# harp_camera_controller_v_1_1.net
KiCad netlist of a schematic drawn in EAGLE
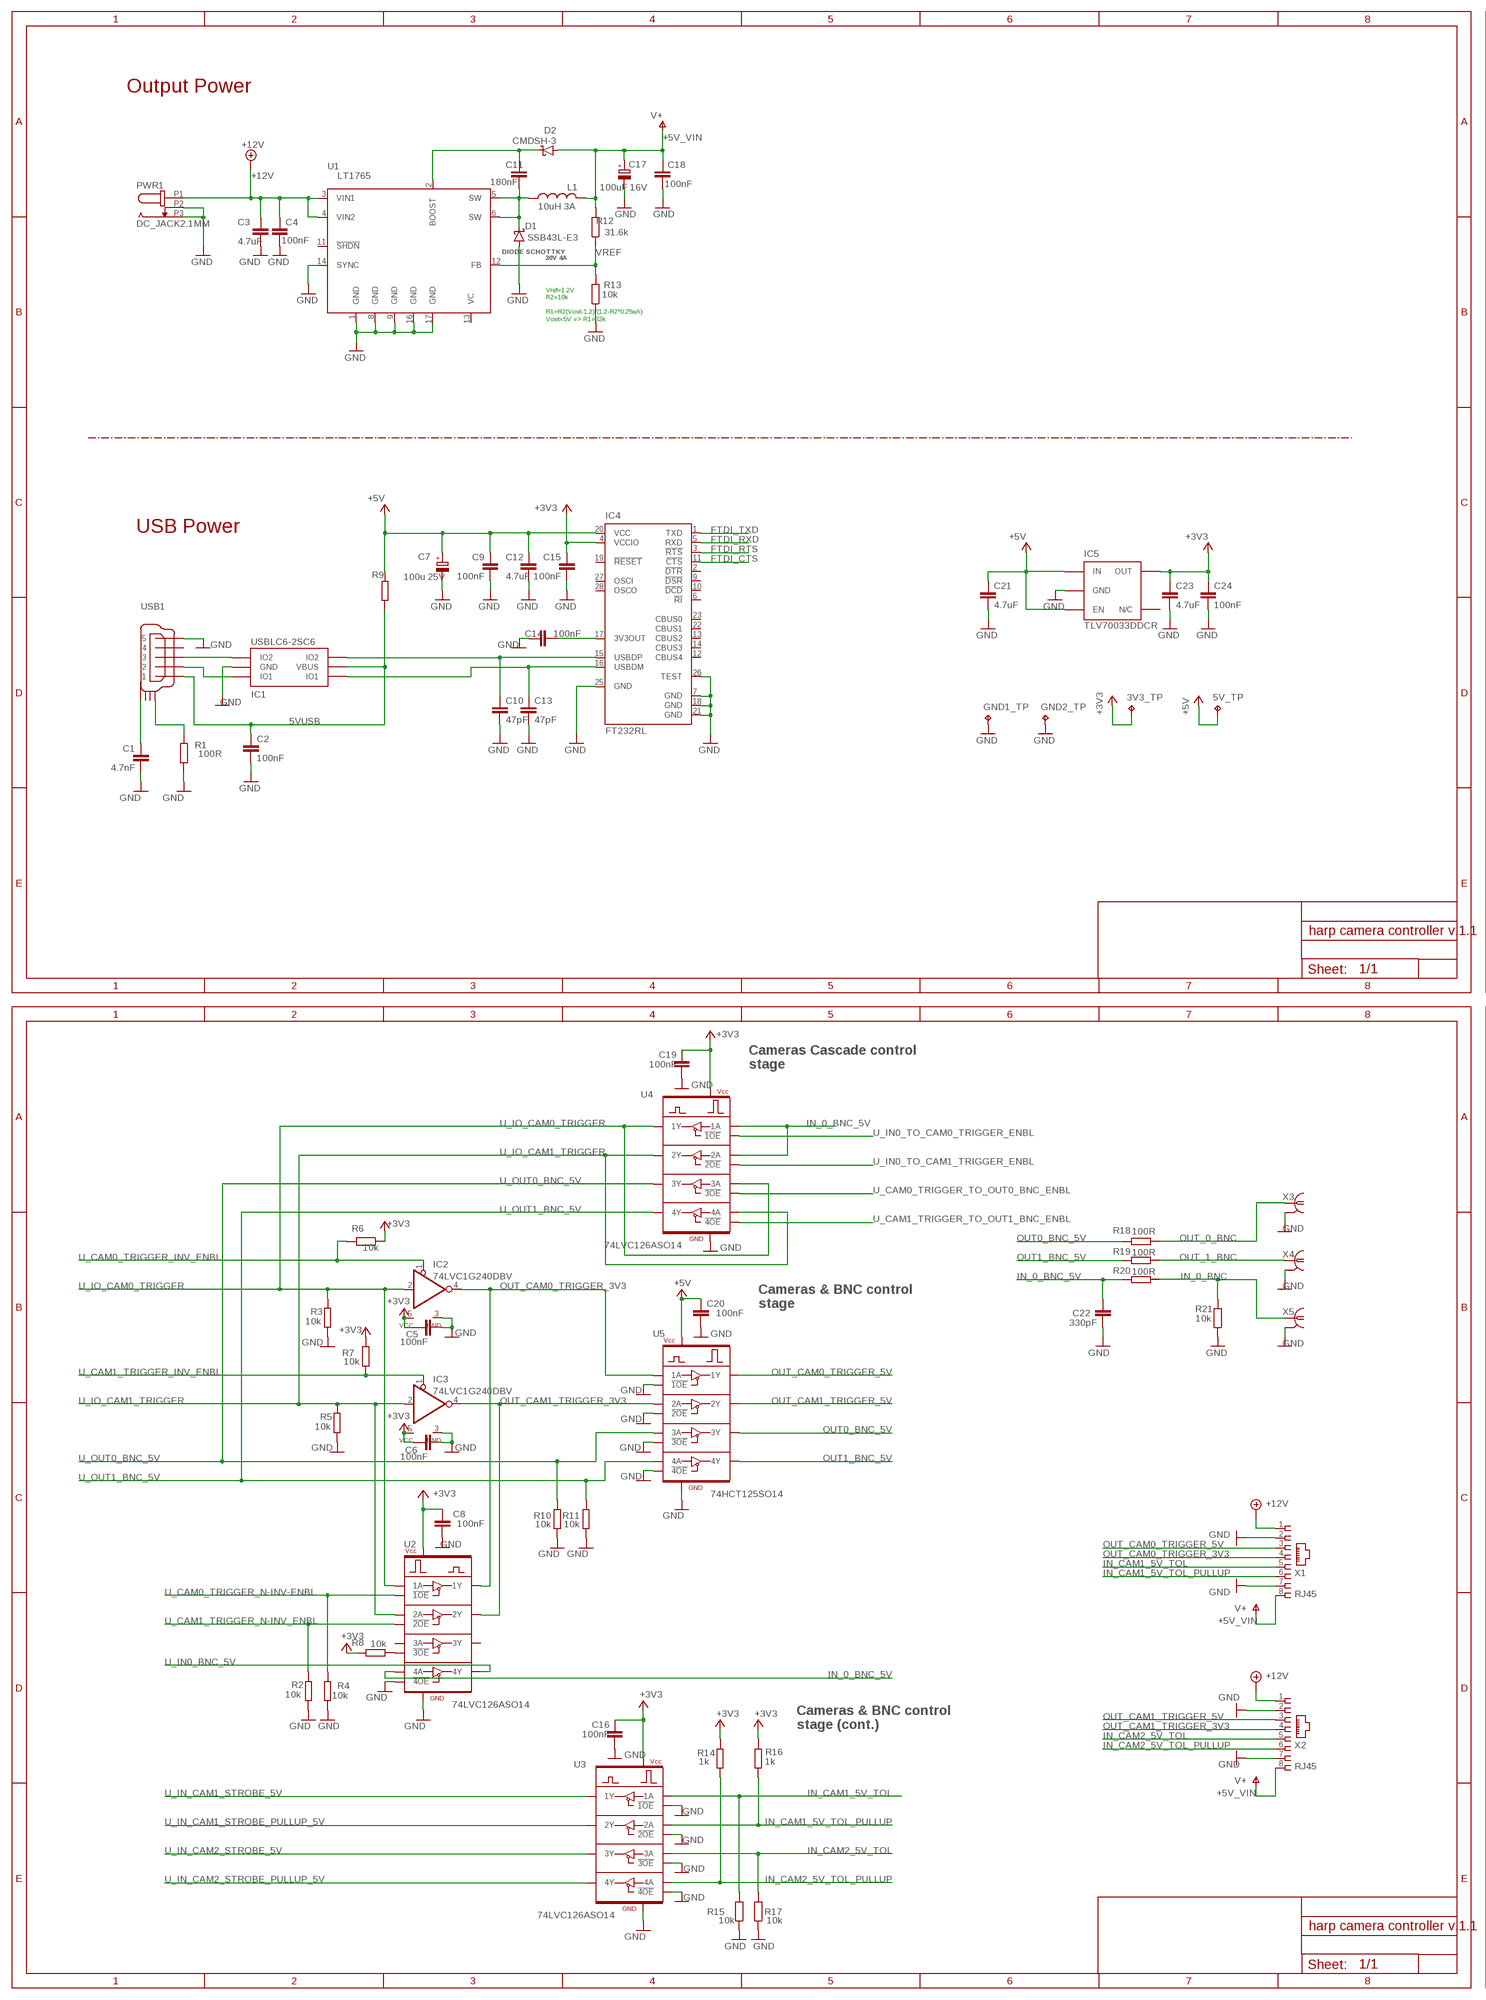
[diagram p0: schematic, sheet 1, part 1 of 2]
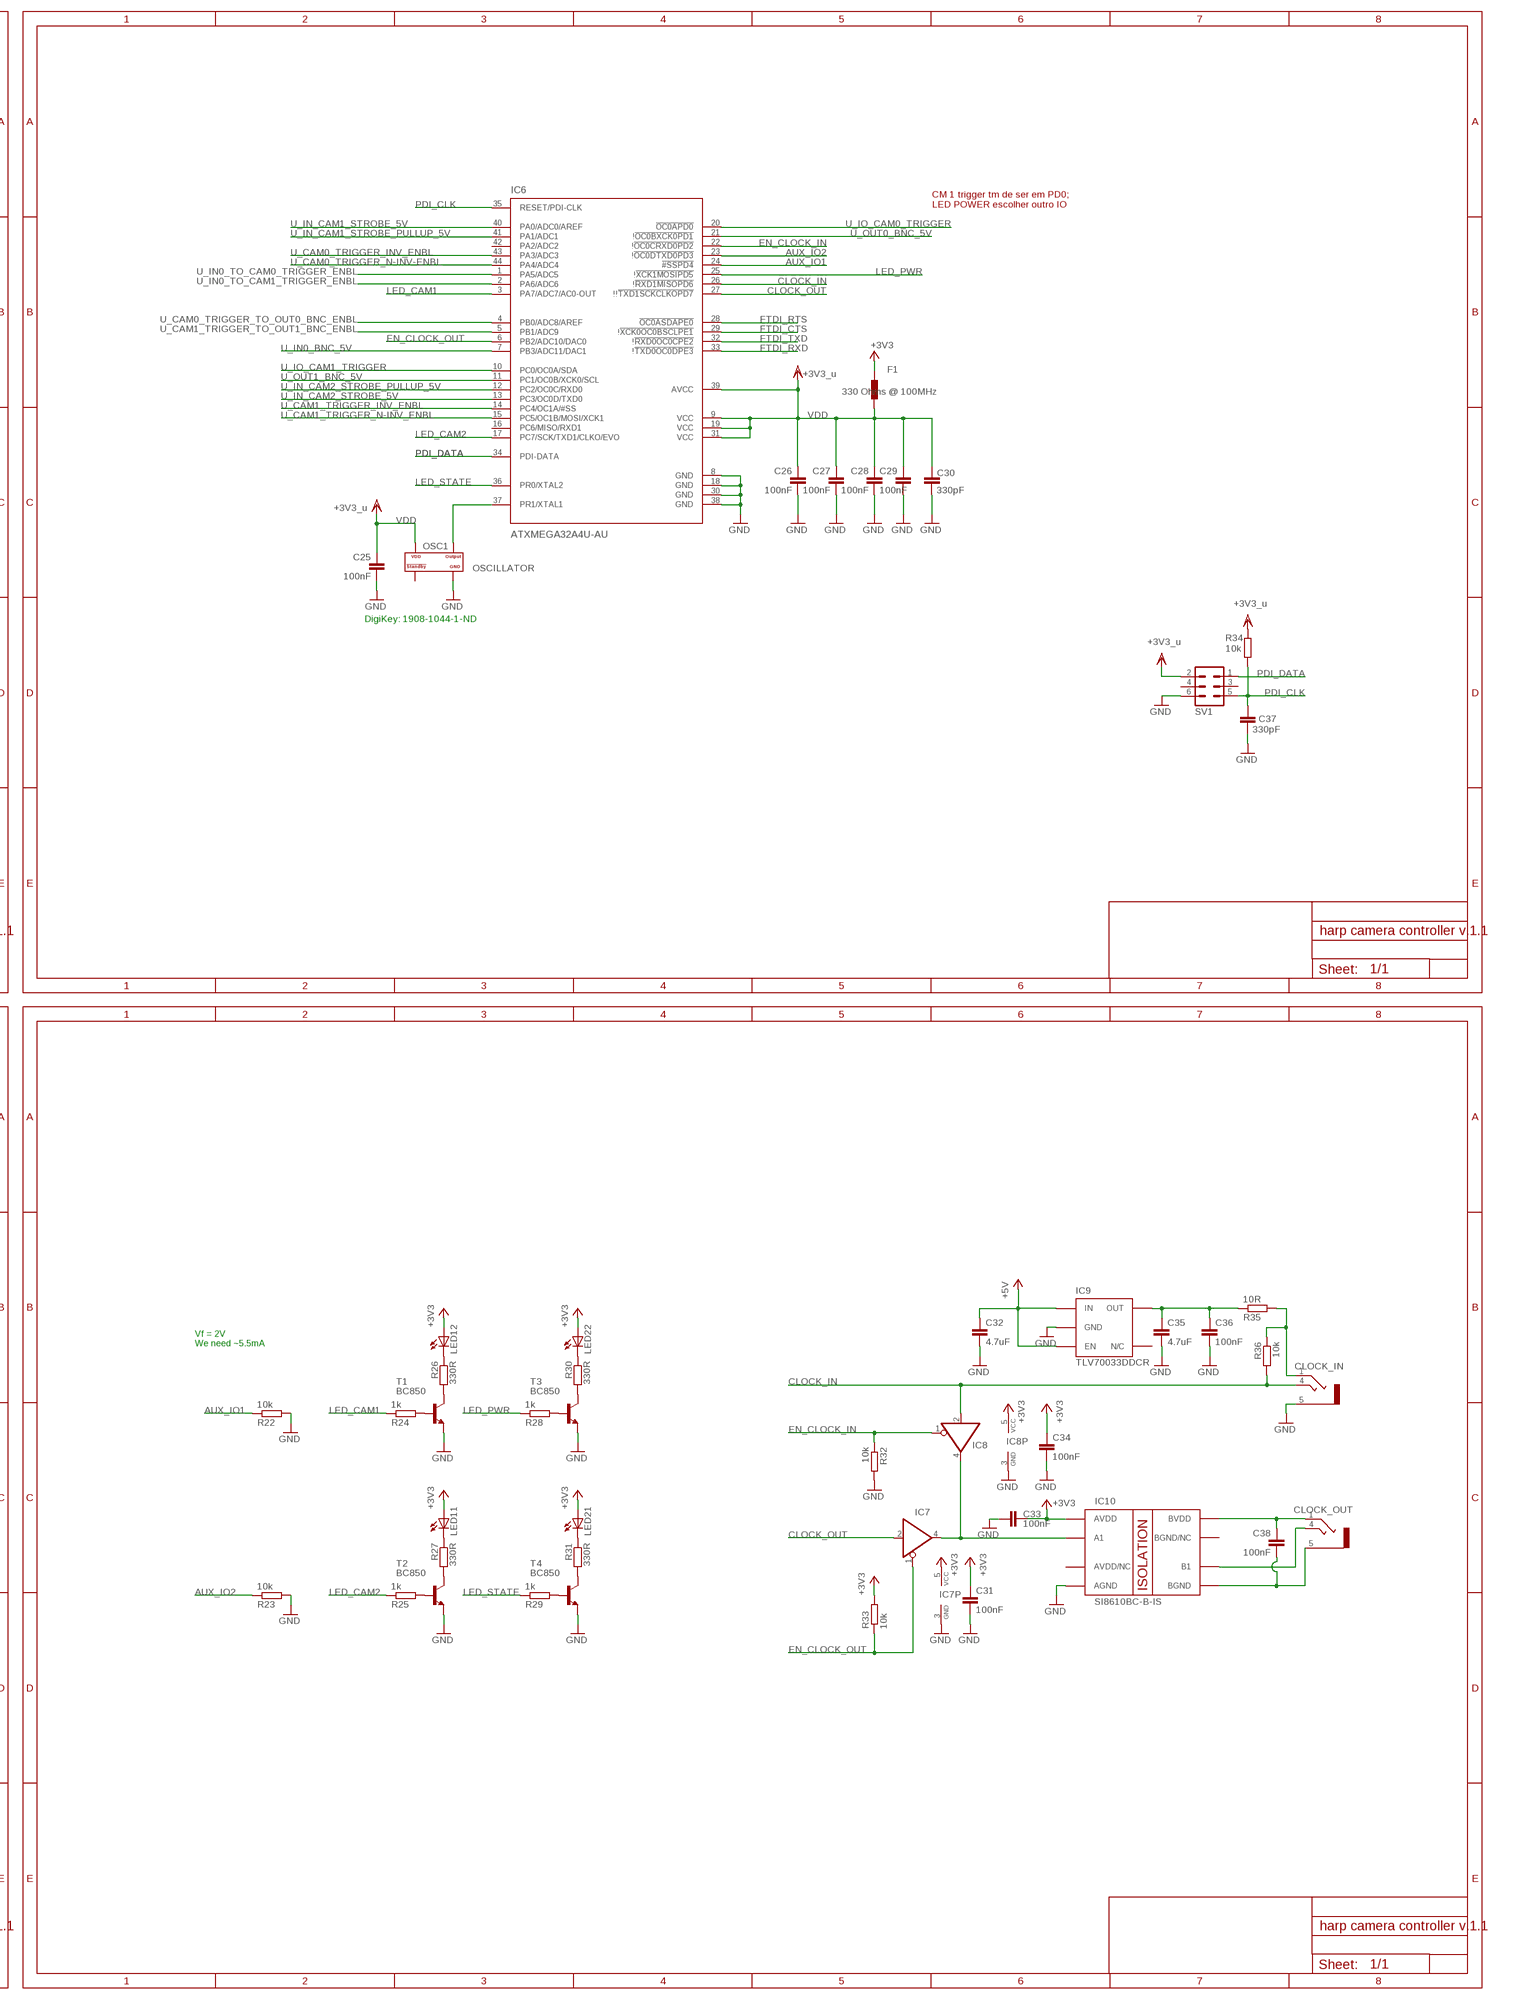
[diagram p1: schematic, sheet 1, part 2 of 2]

(export (version "E")
  (design (tool "Eeschema 10.0.6"))
  (components
    (comp (ref "3V3_TP")
      (value "TPPAD1-13")
      (footprint "eagle-import:P1-13")
      (fields (field (name "MPN") "N.A."))
      (libsource (lib "eagle-import") (part "TPPAD1-13"))
    )
    (comp (ref "5V_TP")
      (value "TPPAD1-13")
      (footprint "eagle-import:P1-13")
      (fields (field (name "MPN") "N.A."))
      (libsource (lib "eagle-import") (part "TPPAD1-13"))
    )
    (comp (ref "C1")
      (value "4.7nF")
      (footprint "eagle-import:C0402")
      (fields (field (name "MPN") "885012205084  "))
      (libsource (lib "eagle-import") (part "C-EUC0402"))
    )
    (comp (ref "C2")
      (value "100nF")
      (footprint "eagle-import:C0402")
      (fields (field (name "MPN") "C1005X7R1H104K050BB"))
      (libsource (lib "eagle-import") (part "C-EUC0402"))
    )
    (comp (ref "C3")
      (value "4.7uF")
      (footprint "eagle-import:C0805")
      (fields (field (name "MPN") "CL21A475KLCLQNC"))
      (libsource (lib "eagle-import") (part "C-EUC0805"))
    )
    (comp (ref "C4")
      (value "100nF")
      (footprint "eagle-import:C0402")
      (fields (field (name "MPN") "C1005X7R1H104K050BB"))
      (libsource (lib "eagle-import") (part "C-EUC0402"))
    )
    (comp (ref "C5")
      (value "100nF")
      (footprint "eagle-import:C0402")
      (fields (field (name "MPN") "C1005X7R1H104K050BB"))
      (libsource (lib "eagle-import") (part "C-EUC0402"))
    )
    (comp (ref "C6")
      (value "100nF")
      (footprint "eagle-import:C0402")
      (fields (field (name "MPN") "C1005X7R1H104K050BB"))
      (libsource (lib "eagle-import") (part "C-EUC0402"))
    )
    (comp (ref "C7")
      (value "100u 25V")
      (footprint "eagle-import:TT2D6")
      (fields (field (name "MPN") "EEU-FM1E101B"))
      (libsource (lib "eagle-import") (part "CPOL-EUTT2D6"))
    )
    (comp (ref "C8")
      (value "100nF")
      (footprint "eagle-import:C0402")
      (fields (field (name "MPN") "C1005X7R1H104K050BB"))
      (libsource (lib "eagle-import") (part "C-EUC0402"))
    )
    (comp (ref "C9")
      (value "100nF")
      (footprint "eagle-import:C0402")
      (fields (field (name "MPN") "C1005X7R1H104K050BB"))
      (libsource (lib "eagle-import") (part "C-EUC0402"))
    )
    (comp (ref "C10")
      (value "47pF")
      (footprint "eagle-import:C0402")
      (fields (field (name "MPN") "04025A470JAT2A"))
      (libsource (lib "eagle-import") (part "C-EUC0402"))
    )
    (comp (ref "C11")
      (value "180nF")
      (footprint "eagle-import:C0603")
      (fields (field (name "MPN") "GCG188R91H184KA01D"))
      (libsource (lib "eagle-import") (part "C-EUC0603"))
    )
    (comp (ref "C12")
      (value "4.7uF")
      (footprint "eagle-import:C0603")
      (fields (field (name "MPN") "C1608X6S1C475K080AC"))
      (libsource (lib "eagle-import") (part "C-EUC0603"))
    )
    (comp (ref "C13")
      (value "47pF")
      (footprint "eagle-import:C0402")
      (fields (field (name "MPN") "04025A470JAT2A"))
      (libsource (lib "eagle-import") (part "C-EUC0402"))
    )
    (comp (ref "C14")
      (value "100nF")
      (footprint "eagle-import:C0402")
      (fields (field (name "MPN") "C1005X7R1H104K050BB"))
      (libsource (lib "eagle-import") (part "C-EUC0402"))
    )
    (comp (ref "C15")
      (value "100nF")
      (footprint "eagle-import:C0402")
      (fields (field (name "MPN") "C1005X7R1H104K050BB"))
      (libsource (lib "eagle-import") (part "C-EUC0402"))
    )
    (comp (ref "C16")
      (value "100nF")
      (footprint "eagle-import:C0402")
      (fields (field (name "MPN") "C1005X7R1H104K050BB"))
      (libsource (lib "eagle-import") (part "C-EUC0402"))
    )
    (comp (ref "C17")
      (value "100uF 16V")
      (footprint "eagle-import:CT7343")
      (fields (field (name "MPN") "T491D107K016AT7280"))
      (libsource (lib "eagle-import") (part "CPOL-EUCT7343"))
    )
    (comp (ref "C18")
      (value "100nF")
      (footprint "eagle-import:C0402")
      (fields (field (name "MPN") "C1005X7R1H104K050BB"))
      (libsource (lib "eagle-import") (part "C-EUC0402"))
    )
    (comp (ref "C19")
      (value "100nF")
      (footprint "eagle-import:C0402")
      (fields (field (name "MPN") "C1005X7R1H104K050BB"))
      (libsource (lib "eagle-import") (part "C-EUC0402"))
    )
    (comp (ref "C20")
      (value "100nF")
      (footprint "eagle-import:C0402")
      (fields (field (name "MPN") "C1005X7R1H104K050BB"))
      (libsource (lib "eagle-import") (part "C-EUC0402"))
    )
    (comp (ref "C21")
      (value "4.7uF")
      (footprint "eagle-import:C0603")
      (fields (field (name "MPN") "C1608X6S1C475K080AC"))
      (libsource (lib "eagle-import") (part "C-EUC0603"))
    )
    (comp (ref "C22")
      (value "330pF")
      (footprint "eagle-import:C0402")
      (fields (field (name "MPN") "C0402C331J5GACTU"))
      (libsource (lib "eagle-import") (part "C-EUC0402"))
    )
    (comp (ref "C23")
      (value "4.7uF")
      (footprint "eagle-import:C0603")
      (fields (field (name "MPN") "C1608X6S1C475K080AC"))
      (libsource (lib "eagle-import") (part "C-EUC0603"))
    )
    (comp (ref "C24")
      (value "100nF")
      (footprint "eagle-import:C0402")
      (fields (field (name "MPN") "C1005X7R1H104K050BB"))
      (libsource (lib "eagle-import") (part "C-EUC0402"))
    )
    (comp (ref "C25")
      (value "100nF")
      (footprint "eagle-import:C0402")
      (fields (field (name "MPN") "C1005X7R1H104K050BB"))
      (libsource (lib "eagle-import") (part "C-EUC0402"))
    )
    (comp (ref "C26")
      (value "100nF")
      (footprint "eagle-import:C0402")
      (fields (field (name "MPN") "C1005X7R1H104K050BB"))
      (libsource (lib "eagle-import") (part "C-EUC0402"))
    )
    (comp (ref "C27")
      (value "100nF")
      (footprint "eagle-import:C0402")
      (fields (field (name "MPN") "C1005X7R1H104K050BB"))
      (libsource (lib "eagle-import") (part "C-EUC0402"))
    )
    (comp (ref "C28")
      (value "100nF")
      (footprint "eagle-import:C0402")
      (fields (field (name "MPN") "C1005X7R1H104K050BB"))
      (libsource (lib "eagle-import") (part "C-EUC0402"))
    )
    (comp (ref "C29")
      (value "100nF")
      (footprint "eagle-import:C0402")
      (fields (field (name "MPN") "C1005X7R1H104K050BB"))
      (libsource (lib "eagle-import") (part "C-EUC0402"))
    )
    (comp (ref "C30")
      (value "330pF")
      (footprint "eagle-import:C0402")
      (fields (field (name "MPN") "C0402C331J5GACTU"))
      (libsource (lib "eagle-import") (part "C-EUC0402"))
    )
    (comp (ref "C31")
      (value "100nF")
      (footprint "eagle-import:C0402")
      (fields (field (name "MPN") "C1005X7R1H104K050BB"))
      (libsource (lib "eagle-import") (part "C-EUC0402"))
    )
    (comp (ref "C32")
      (value "4.7uF")
      (footprint "eagle-import:C0603")
      (fields (field (name "MPN") "C1608X6S1C475K080AC"))
      (libsource (lib "eagle-import") (part "C-EUC0603"))
    )
    (comp (ref "C33")
      (value "100nF")
      (footprint "eagle-import:C0402")
      (fields (field (name "MPN") "C1005X7R1H104K050BB"))
      (libsource (lib "eagle-import") (part "C-EUC0402"))
    )
    (comp (ref "C34")
      (value "100nF")
      (footprint "eagle-import:C0402")
      (fields (field (name "MPN") "C1005X7R1H104K050BB"))
      (libsource (lib "eagle-import") (part "C-EUC0402"))
    )
    (comp (ref "C35")
      (value "4.7uF")
      (footprint "eagle-import:C0603")
      (fields (field (name "MPN") "C1608X6S1C475K080AC"))
      (libsource (lib "eagle-import") (part "C-EUC0603"))
    )
    (comp (ref "C36")
      (value "100nF")
      (footprint "eagle-import:C0402")
      (fields (field (name "MPN") "C1005X7R1H104K050BB"))
      (libsource (lib "eagle-import") (part "C-EUC0402"))
    )
    (comp (ref "C37")
      (value "330pF")
      (footprint "eagle-import:C0402")
      (fields (field (name "MPN") "C0402C331J5GACTU"))
      (libsource (lib "eagle-import") (part "C-EUC0402"))
    )
    (comp (ref "C38")
      (value "100nF")
      (footprint "eagle-import:C0402")
      (fields (field (name "MPN") "C1005X7R1H104K050BB"))
      (libsource (lib "eagle-import") (part "C-EUC0402"))
    )
    (comp (ref "CLOCK_IN")
      (value "CLCK_JACK")
      (footprint "eagle-import:35RASMT2BHNTRX")
      (fields (field (name "MPN") "35RASMT2BHNTRX"))
      (libsource (lib "eagle-import") (part "STEREO_JACK"))
    )
    (comp (ref "CLOCK_OUT")
      (value "CLCK_JACK")
      (footprint "eagle-import:35RASMT2BHNTRX")
      (fields (field (name "MPN") "35RASMT2BHNTRX"))
      (libsource (lib "eagle-import") (part "STEREO_JACK"))
    )
    (comp (ref "D1")
      (value "SSB43L-E3")
      (footprint "eagle-import:SMB")
      (fields (field (name "MPN") "SSB43L-E3/52T"))
      (libsource (lib "eagle-import") (part "SCHOTTKY-DIODE"))
    )
    (comp (ref "D2")
      (value "CMDSH-3")
      (footprint "eagle-import:SOD323-R")
      (libsource (lib "eagle-import") (part "SCHOTTKY-DIODESOD323"))
    )
    (comp (ref "F1")
      (value "330 Ohms @ 100MHz")
      (footprint "eagle-import:R0603")
      (fields (field (name "MPN") "BLM18SG331TN1D"))
      (libsource (lib "eagle-import") (part "BLM15HF0603"))
    )
    (comp (ref "GND1_TP")
      (value "TPPAD1-13")
      (footprint "eagle-import:P1-13")
      (fields (field (name "MPN") "N.A."))
      (libsource (lib "eagle-import") (part "TPPAD1-13"))
    )
    (comp (ref "GND2_TP")
      (value "TPPAD1-13")
      (footprint "eagle-import:P1-13")
      (fields (field (name "MPN") "N.A."))
      (libsource (lib "eagle-import") (part "TPPAD1-13"))
    )
    (comp (ref "IC1")
      (value "USBLC6-2SC6")
      (footprint "eagle-import:SOT23-6L")
      (libsource (lib "eagle-import") (part "USBLC6-2"))
    )
    (comp (ref "IC2")
      (value "74LVC1G240DBV")
      (footprint "eagle-import:SOT23-5")
      (fields (field (name "MPN") "SN74LVC1G240DBVR"))
      (libsource (lib "eagle-import") (part "74LVC1G240DBV"))
    )
    (comp (ref "IC3")
      (value "74LVC1G240DBV")
      (footprint "eagle-import:SOT23-5")
      (fields (field (name "MPN") "SN74LVC1G240DBVR"))
      (libsource (lib "eagle-import") (part "74LVC1G240DBV"))
    )
    (comp (ref "IC4")
      (value "FT232RL")
      (footprint "eagle-import:SSOP28")
      (fields (field (name "MPN") "FT232RL-REEL"))
      (libsource (lib "eagle-import") (part "FT232RL"))
    )
    (comp (ref "IC5")
      (value "TLV70033DDCR")
      (footprint "eagle-import:TSOT23-5")
      (libsource (lib "eagle-import") (part "TLV700XX"))
    )
    (comp (ref "IC6")
      (value "ATXMEGA32A4U-AU")
      (footprint "eagle-import:QFP80P1200X1200X120-44N")
      (fields (field (name "MPN") "ATXMEGA32A4U-AUR"))
      (libsource (lib "eagle-import") (part "AT-XMEGA-XXA4-AU"))
    )
    (comp (ref "IC7")
      (value "SN74LVC1G125DBVT")
      (footprint "eagle-import:SOT23-5")
      (fields
        (field (name "DIGIKEY_PN") "296-26595-1-ND")
        (field (name "MOUSER_PN") "595-SN74LVC1G125DBVT")
        (field (name "MPN") "SN74LVC1G125DBVT")
      )
      (libsource (lib "eagle-import") (part "741G125DBVAHC"))
    )
    (comp (ref "IC8")
      (value "SN74LVC1G125DBVT")
      (footprint "eagle-import:SOT23-5")
      (fields
        (field (name "DIGIKEY_PN") "296-26595-1-ND")
        (field (name "MOUSER_PN") "595-SN74LVC1G125DBVT")
        (field (name "MPN") "SN74LVC1G125DBVT")
      )
      (libsource (lib "eagle-import") (part "741G125DBVAHC"))
    )
    (comp (ref "IC9")
      (value "TLV70033DDCR")
      (footprint "eagle-import:TSOT23-5")
      (libsource (lib "eagle-import") (part "TLV700XX"))
    )
    (comp (ref "IC10")
      (value "SI8610BC-B-IS")
      (footprint "eagle-import:SO-08")
      (fields (field (name "MPN") "SI8610EC-B-IS"))
      (libsource (lib "eagle-import") (part "SI8610"))
    )
    (comp (ref "L1")
      (value "10uH 3A")
      (footprint "eagle-import:L_IHLP_PADS")
      (fields (field (name "MPN") "IHLP2525CZER100M01"))
      (libsource (lib "eagle-import") (part "L_IHLP2525CZER100M01"))
    )
    (comp (ref "LED1")
      (value "RED_LEDs")
      (footprint "eagle-import:569-011X-X00_LED_ARRAY")
      (fields (field (name "MPN") "5690-111-100F"))
      (libsource (lib "eagle-import") (part "LED_2X_VERTICAL"))
    )
    (comp (ref "LED2")
      (value "RED_LEDs")
      (footprint "eagle-import:569-011X-X00_LED_ARRAY")
      (fields (field (name "MPN") "5690-111-100F"))
      (libsource (lib "eagle-import") (part "LED_2X_VERTICAL"))
    )
    (comp (ref "OSC1")
      (value "OSCILLATOR")
      (footprint "eagle-import:OSCILLATOR_3.2X2.5")
      (fields (field (name "MPN") "O 32,0-JT32C-A-K-3,3-LF"))
      (libsource (lib "eagle-import") (part "OSCILLATOR"))
    )
    (comp (ref "PWR1")
      (value "DC_JACK2.1MM")
      (footprint "eagle-import:DC_POWER_INPUT_2.1MM")
      (fields (field (name "MPN") "163-179PH-EX"))
      (libsource (lib "eagle-import") (part "DC_JACK2.1MM"))
    )
    (comp (ref "R1")
      (value "100R")
      (footprint "eagle-import:R0603")
      (fields (field (name "MPN") "ERJ-3EKF1000V"))
      (libsource (lib "eagle-import") (part "R-EU_R0603"))
    )
    (comp (ref "R2")
      (value "10k")
      (footprint "eagle-import:R0402")
      (fields (field (name "MPN") "CRCW040210K0FKED"))
      (libsource (lib "eagle-import") (part "R-EU_R0402"))
    )
    (comp (ref "R3")
      (value "10k")
      (footprint "eagle-import:R0402")
      (fields (field (name "MPN") "CRCW040210K0FKED"))
      (libsource (lib "eagle-import") (part "R-EU_R0402"))
    )
    (comp (ref "R4")
      (value "10k")
      (footprint "eagle-import:R0402")
      (fields (field (name "MPN") "CRCW040210K0FKED"))
      (libsource (lib "eagle-import") (part "R-EU_R0402"))
    )
    (comp (ref "R5")
      (value "10k")
      (footprint "eagle-import:R0402")
      (fields (field (name "MPN") "CRCW040210K0FKED"))
      (libsource (lib "eagle-import") (part "R-EU_R0402"))
    )
    (comp (ref "R6")
      (value "10k")
      (footprint "eagle-import:R0402")
      (fields (field (name "MPN") "CRCW040210K0FKED"))
      (libsource (lib "eagle-import") (part "R-EU_R0402"))
    )
    (comp (ref "R7")
      (value "10k")
      (footprint "eagle-import:R0402")
      (fields (field (name "MPN") "CRCW040210K0FKED"))
      (libsource (lib "eagle-import") (part "R-EU_R0402"))
    )
    (comp (ref "R8")
      (value "10k")
      (footprint "eagle-import:R0402")
      (fields (field (name "MPN") "CRCW040210K0FKED"))
      (libsource (lib "eagle-import") (part "R-EU_R0402"))
    )
    (comp (ref "R9")
      (value "40R@100MHz")
      (footprint "eagle-import:R0805")
      (fields (field (name "MPN") "MI0805K400R-10"))
      (libsource (lib "eagle-import") (part "R-EU_R0805"))
    )
    (comp (ref "R10")
      (value "10k")
      (footprint "eagle-import:R0402")
      (fields (field (name "MPN") "CRCW040210K0FKED"))
      (libsource (lib "eagle-import") (part "R-EU_R0402"))
    )
    (comp (ref "R11")
      (value "10k")
      (footprint "eagle-import:R0402")
      (fields (field (name "MPN") "CRCW040210K0FKED"))
      (libsource (lib "eagle-import") (part "R-EU_R0402"))
    )
    (comp (ref "R12")
      (value "31.6k")
      (footprint "eagle-import:R0402")
      (fields (field (name "MPN") "RC0402FR-0740K2L"))
      (libsource (lib "eagle-import") (part "R-EU_R0402"))
    )
    (comp (ref "R13")
      (value "10k")
      (footprint "eagle-import:R0402")
      (fields (field (name "MPN") "CRCW040210K0FKED"))
      (libsource (lib "eagle-import") (part "R-EU_R0402"))
    )
    (comp (ref "R14")
      (value "1k")
      (footprint "eagle-import:R0402")
      (fields (field (name "MPN") "CRCW04021K00FKEDC"))
      (libsource (lib "eagle-import") (part "R-EU_R0402"))
    )
    (comp (ref "R15")
      (value "10k")
      (footprint "eagle-import:R0402")
      (fields (field (name "MPN") "CRCW040210K0FKED"))
      (libsource (lib "eagle-import") (part "R-EU_R0402"))
    )
    (comp (ref "R16")
      (value "1k")
      (footprint "eagle-import:R0402")
      (fields (field (name "MPN") "CRCW04021K00FKEDC"))
      (libsource (lib "eagle-import") (part "R-EU_R0402"))
    )
    (comp (ref "R17")
      (value "10k")
      (footprint "eagle-import:R0402")
      (fields (field (name "MPN") "CRCW040210K0FKED"))
      (libsource (lib "eagle-import") (part "R-EU_R0402"))
    )
    (comp (ref "R18")
      (value "100R")
      (footprint "eagle-import:R0603")
      (fields (field (name "MPN") "ERJ-3EKF1000V"))
      (libsource (lib "eagle-import") (part "R-EU_R0603"))
    )
    (comp (ref "R19")
      (value "100R")
      (footprint "eagle-import:R0603")
      (fields (field (name "MPN") "ERJ-3EKF1000V"))
      (libsource (lib "eagle-import") (part "R-EU_R0603"))
    )
    (comp (ref "R20")
      (value "100R")
      (footprint "eagle-import:R0603")
      (fields (field (name "MPN") "ERJ-3EKF1000V"))
      (libsource (lib "eagle-import") (part "R-EU_R0603"))
    )
    (comp (ref "R21")
      (value "10k")
      (footprint "eagle-import:R0402")
      (fields (field (name "MPN") "CRCW040210K0FKED"))
      (libsource (lib "eagle-import") (part "R-EU_R0402"))
    )
    (comp (ref "R22")
      (value "10k")
      (footprint "eagle-import:R0402")
      (fields (field (name "MPN") "CRCW040210K0FKED"))
      (libsource (lib "eagle-import") (part "R-EU_R0402"))
    )
    (comp (ref "R23")
      (value "10k")
      (footprint "eagle-import:R0402")
      (fields (field (name "MPN") "CRCW040210K0FKED"))
      (libsource (lib "eagle-import") (part "R-EU_R0402"))
    )
    (comp (ref "R24")
      (value "1k")
      (footprint "eagle-import:R0402")
      (fields (field (name "MPN") "CRCW04021K00FKEDC"))
      (libsource (lib "eagle-import") (part "R-EU_R0402"))
    )
    (comp (ref "R25")
      (value "1k")
      (footprint "eagle-import:R0402")
      (fields (field (name "MPN") "CRCW04021K00FKEDC"))
      (libsource (lib "eagle-import") (part "R-EU_R0402"))
    )
    (comp (ref "R26")
      (value "330R")
      (footprint "eagle-import:R0402")
      (fields (field (name "MPN") "RC0402FR-07330RL "))
      (libsource (lib "eagle-import") (part "R-EU_R0402"))
    )
    (comp (ref "R27")
      (value "330R")
      (footprint "eagle-import:R0402")
      (fields (field (name "MPN") "RC0402FR-07330RL "))
      (libsource (lib "eagle-import") (part "R-EU_R0402"))
    )
    (comp (ref "R28")
      (value "1k")
      (footprint "eagle-import:R0402")
      (fields (field (name "MPN") "CRCW04021K00FKEDC"))
      (libsource (lib "eagle-import") (part "R-EU_R0402"))
    )
    (comp (ref "R29")
      (value "1k")
      (footprint "eagle-import:R0402")
      (fields (field (name "MPN") "CRCW04021K00FKEDC"))
      (libsource (lib "eagle-import") (part "R-EU_R0402"))
    )
    (comp (ref "R30")
      (value "330R")
      (footprint "eagle-import:R0402")
      (fields (field (name "MPN") "RC0402FR-07330RL "))
      (libsource (lib "eagle-import") (part "R-EU_R0402"))
    )
    (comp (ref "R31")
      (value "330R")
      (footprint "eagle-import:R0402")
      (fields (field (name "MPN") "RC0402FR-07330RL "))
      (libsource (lib "eagle-import") (part "R-EU_R0402"))
    )
    (comp (ref "R32")
      (value "10k")
      (footprint "eagle-import:R0402")
      (fields (field (name "MPN") "CRCW040210K0FKED"))
      (libsource (lib "eagle-import") (part "R-EU_R0402"))
    )
    (comp (ref "R33")
      (value "10k")
      (footprint "eagle-import:R0402")
      (fields (field (name "MPN") "CRCW040210K0FKED"))
      (libsource (lib "eagle-import") (part "R-EU_R0402"))
    )
    (comp (ref "R34")
      (value "10k")
      (footprint "eagle-import:R0402")
      (fields (field (name "MPN") "CRCW040210K0FKED"))
      (libsource (lib "eagle-import") (part "R-EU_R0402"))
    )
    (comp (ref "R35")
      (value "10R")
      (footprint "eagle-import:R0402")
      (fields (field (name "MPN") "CRCW040210R0FKEDC"))
      (libsource (lib "eagle-import") (part "R-EU_R0402"))
    )
    (comp (ref "R36")
      (value "10k")
      (footprint "eagle-import:R0402")
      (fields (field (name "MPN") "CRCW040210K0FKED"))
      (libsource (lib "eagle-import") (part "R-EU_R0402"))
    )
    (comp (ref "SV1")
      (value "PROG HEADER")
      (footprint "eagle-import:MA03-2")
      (fields (field (name "MPN") "61300621121"))
      (libsource (lib "eagle-import") (part "MA03-2"))
    )
    (comp (ref "T1")
      (value "BC850")
      (footprint "eagle-import:SOT23")
      (fields (field (name "MPN") "BC850C,215"))
      (libsource (lib "eagle-import") (part "BC850"))
    )
    (comp (ref "T2")
      (value "BC850")
      (footprint "eagle-import:SOT23")
      (fields (field (name "MPN") "BC850C,215"))
      (libsource (lib "eagle-import") (part "BC850"))
    )
    (comp (ref "T3")
      (value "BC850")
      (footprint "eagle-import:SOT23")
      (fields (field (name "MPN") "BC850C,215"))
      (libsource (lib "eagle-import") (part "BC850"))
    )
    (comp (ref "T4")
      (value "BC850")
      (footprint "eagle-import:SOT23")
      (fields (field (name "MPN") "BC850C,215"))
      (libsource (lib "eagle-import") (part "BC850"))
    )
    (comp (ref "U1")
      (value "LT1765")
      (footprint "eagle-import:TSSOP16EXP")
      (fields (field (name "MPN") "LT1765EFE#PBF"))
      (libsource (lib "eagle-import") (part "LT1765"))
    )
    (comp (ref "U2")
      (value "74LVC126ASO14")
      (footprint "eagle-import:SO14")
      (fields (field (name "MPN") "74LVC126AD,118  "))
      (libsource (lib "eagle-import") (part "74LVC126ASO14"))
    )
    (comp (ref "U3")
      (value "74LVC126ASO14")
      (footprint "eagle-import:SO14")
      (fields (field (name "MPN") "74LVC126AD,118  "))
      (libsource (lib "eagle-import") (part "74LVC126ASO14"))
    )
    (comp (ref "U4")
      (value "74LVC126ASO14")
      (footprint "eagle-import:SO14")
      (fields (field (name "MPN") "74LVC126AD,118  "))
      (libsource (lib "eagle-import") (part "74LVC126ASO14"))
    )
    (comp (ref "U5")
      (value "74HCT125SO14")
      (footprint "eagle-import:SO14")
      (fields (field (name "MPN") "74HCT125D,653"))
      (libsource (lib "eagle-import") (part "74HCT125SO14"))
    )
    (comp (ref "USB1")
      (value "mini USB")
      (footprint "eagle-import:240-0002-1")
      (fields (field (name "MPN") "UX60-MB-5S8 "))
      (libsource (lib "eagle-import") (part "USB_MINI_B"))
    )
    (comp (ref "X1")
      (value "RJ45")
      (footprint "eagle-import:RJ45-NO-SHIELD")
      (fields (field (name "MPN") "215877-1"))
      (libsource (lib "eagle-import") (part "RJ45"))
    )
    (comp (ref "X2")
      (value "RJ45")
      (footprint "eagle-import:RJ45-NO-SHIELD")
      (fields (field (name "MPN") "215877-1"))
      (libsource (lib "eagle-import") (part "RJ45"))
    )
    (comp (ref "X3")
      (value "BNC plug")
      (footprint "eagle-import:0731000105")
      (fields (field (name "MPN") "73100-0105"))
      (libsource (lib "eagle-import") (part "BNC_0731000105"))
    )
    (comp (ref "X4")
      (value "BNC plug")
      (footprint "eagle-import:0731000105")
      (fields (field (name "MPN") "73100-0105"))
      (libsource (lib "eagle-import") (part "BNC_0731000105"))
    )
    (comp (ref "X5")
      (value "BNC plug")
      (footprint "eagle-import:0731000105")
      (fields (field (name "MPN") "73100-0105"))
      (libsource (lib "eagle-import") (part "BNC_0731000105"))
    )
  )
  (nets
    (net (code "1") (name "+3V3") (class "Default")
      (node (ref "3V3_TP") (pin "TP") (pinfunction "TP_TP") (pintype "input"))
      (node (ref "C15") (pin "1") (pinfunction "1_1") (pintype "passive"))
      (node (ref "C16") (pin "1") (pinfunction "1_1") (pintype "passive"))
      (node (ref "C19") (pin "1") (pinfunction "1_1") (pintype "passive"))
      (node (ref "C23") (pin "1") (pinfunction "1_1") (pintype "passive"))
      (node (ref "C24") (pin "1") (pinfunction "1_1") (pintype "passive"))
      (node (ref "C31") (pin "1") (pinfunction "1_1") (pintype "passive"))
      (node (ref "C33") (pin "1") (pinfunction "1_1") (pintype "passive"))
      (node (ref "C34") (pin "1") (pinfunction "1_1") (pintype "passive"))
      (node (ref "C5") (pin "1") (pinfunction "1_1") (pintype "passive"))
      (node (ref "C6") (pin "1") (pinfunction "1_1") (pintype "passive"))
      (node (ref "C8") (pin "1") (pinfunction "1_1") (pintype "passive"))
      (node (ref "F1") (pin "2") (pinfunction "2_2") (pintype "passive"))
      (node (ref "IC10") (pin "1") (pinfunction "AVDD_1") (pintype "bidirectional"))
      (node (ref "IC2") (pin "5") (pinfunction "VCC_5") (pintype "input"))
      (node (ref "IC3") (pin "5") (pinfunction "VCC_5") (pintype "input"))
      (node (ref "IC4") (pin "4") (pinfunction "VCCIO_4") (pintype "input"))
      (node (ref "IC5") (pin "5") (pinfunction "OUT_5") (pintype "bidirectional"))
      (node (ref "IC7") (pin "5") (pinfunction "VCC_5") (pintype "power_in"))
      (node (ref "IC8") (pin "5") (pinfunction "VCC_5") (pintype "power_in"))
      (node (ref "LED1") (pin "A1") (pinfunction "A_A1") (pintype "passive"))
      (node (ref "LED1") (pin "A2") (pinfunction "A_A2") (pintype "passive"))
      (node (ref "LED2") (pin "A1") (pinfunction "A_A1") (pintype "passive"))
      (node (ref "LED2") (pin "A2") (pinfunction "A_A2") (pintype "passive"))
      (node (ref "R14") (pin "1") (pinfunction "1_1") (pintype "passive"))
      (node (ref "R16") (pin "1") (pinfunction "1_1") (pintype "passive"))
      (node (ref "R33") (pin "2") (pinfunction "2_2") (pintype "passive"))
      (node (ref "R6") (pin "1") (pinfunction "1_1") (pintype "passive"))
      (node (ref "R7") (pin "1") (pinfunction "1_1") (pintype "passive"))
      (node (ref "R8") (pin "1") (pinfunction "1_1") (pintype "passive"))
      (node (ref "U2") (pin "14") (pinfunction "VCC_14") (pintype "input"))
      (node (ref "U3") (pin "14") (pinfunction "VCC_14") (pintype "input"))
      (node (ref "U4") (pin "14") (pinfunction "VCC_14") (pintype "input"))
    )
    (net (code "2") (name "+3V3_u") (class "Default")
      (node (ref "C25") (pin "1") (pinfunction "1_1") (pintype "passive"))
      (node (ref "C26") (pin "1") (pinfunction "1_1") (pintype "passive"))
      (node (ref "C27") (pin "1") (pinfunction "1_1") (pintype "passive"))
      (node (ref "C28") (pin "1") (pinfunction "1_1") (pintype "passive"))
      (node (ref "C29") (pin "1") (pinfunction "1_1") (pintype "passive"))
      (node (ref "C30") (pin "1") (pinfunction "1_1") (pintype "passive"))
      (node (ref "F1") (pin "1") (pinfunction "1_1") (pintype "passive"))
      (node (ref "IC6") (pin "19") (pinfunction "VCC_19") (pintype "power_in"))
      (node (ref "IC6") (pin "31") (pinfunction "VCC_31") (pintype "power_in"))
      (node (ref "IC6") (pin "39") (pinfunction "AVCC_39") (pintype "power_in"))
      (node (ref "IC6") (pin "9") (pinfunction "VCC_9") (pintype "power_in"))
      (node (ref "OSC1") (pin "P$4") (pinfunction "VDD_P$4") (pintype "passive"))
      (node (ref "R34") (pin "2") (pinfunction "2_2") (pintype "passive"))
      (node (ref "SV1") (pin "2") (pinfunction "2_2") (pintype "passive"))
    )
    (net (code "3") (name "+5V") (class "Default")
      (node (ref "5V_TP") (pin "TP") (pinfunction "TP_TP") (pintype "input"))
      (node (ref "C12") (pin "1") (pinfunction "1_1") (pintype "passive"))
      (node (ref "C20") (pin "1") (pinfunction "1_1") (pintype "passive"))
      (node (ref "C21") (pin "1") (pinfunction "1_1") (pintype "passive"))
      (node (ref "C32") (pin "1") (pinfunction "1_1") (pintype "passive"))
      (node (ref "C7") (pin "+") (pinfunction "+_+") (pintype "passive"))
      (node (ref "C9") (pin "1") (pinfunction "1_1") (pintype "passive"))
      (node (ref "IC4") (pin "20") (pinfunction "VCC_20") (pintype "input"))
      (node (ref "IC5") (pin "1") (pinfunction "IN_1") (pintype "bidirectional"))
      (node (ref "IC5") (pin "3") (pinfunction "EN_3") (pintype "bidirectional"))
      (node (ref "IC9") (pin "1") (pinfunction "IN_1") (pintype "bidirectional"))
      (node (ref "IC9") (pin "3") (pinfunction "EN_3") (pintype "bidirectional"))
      (node (ref "R9") (pin "1") (pinfunction "1_1") (pintype "passive"))
      (node (ref "U5") (pin "14") (pinfunction "VCC_14") (pintype "input"))
    )
    (net (code "4") (name "+12V") (class "Default")
      (node (ref "C3") (pin "1") (pinfunction "1_1") (pintype "passive"))
      (node (ref "C4") (pin "1") (pinfunction "1_1") (pintype "passive"))
      (node (ref "PWR1") (pin "P1") (pinfunction "1_P1") (pintype "passive"))
      (node (ref "U1") (pin "3") (pinfunction "VIN1_3") (pintype "bidirectional"))
      (node (ref "U1") (pin "4") (pinfunction "VIN2_4") (pintype "bidirectional"))
      (node (ref "X1") (pin "1") (pinfunction "1_1") (pintype "passive"))
      (node (ref "X2") (pin "1") (pinfunction "1_1") (pintype "passive"))
    )
    (net (code "5") (name "/5VUSB") (class "Default")
      (node (ref "C2") (pin "1") (pinfunction "1_1") (pintype "passive"))
      (node (ref "IC1") (pin "P$5") (pinfunction "VBUS_P$5") (pintype "bidirectional"))
      (node (ref "R9") (pin "2") (pinfunction "2_2") (pintype "passive"))
      (node (ref "USB1") (pin "P$1") (pinfunction "1_P$1") (pintype "bidirectional"))
    )
    (net (code "6") (name "/AUX_IO1") (class "Default")
      (node (ref "IC6") (pin "24") (pinfunction "~{#SSPD4}_24") (pintype "bidirectional"))
      (node (ref "R22") (pin "1") (pinfunction "1_1") (pintype "passive"))
    )
    (net (code "7") (name "/AUX_IO2") (class "Default")
      (node (ref "IC6") (pin "23") (pinfunction "~OC0DTXD0PD3_23") (pintype "bidirectional"))
      (node (ref "R23") (pin "1") (pinfunction "1_1") (pintype "passive"))
    )
    (net (code "8") (name "/CLOCK_IN") (class "Default")
      (node (ref "CLOCK_IN") (pin "4") (pinfunction "4_4") (pintype "passive"))
      (node (ref "IC6") (pin "26") (pinfunction "~RXD1MISOPD6_26") (pintype "bidirectional"))
      (node (ref "IC8") (pin "2") (pinfunction "I_2") (pintype "input"))
      (node (ref "R36") (pin "2") (pinfunction "2_2") (pintype "passive"))
    )
    (net (code "9") (name "/CLOCK_OUT") (class "Default")
      (node (ref "IC6") (pin "27") (pinfunction "~~{TXD1SCKCLKOPD7}_27") (pintype "bidirectional"))
      (node (ref "IC7") (pin "2") (pinfunction "I_2") (pintype "input"))
    )
    (net (code "10") (name "/EN_CLOCK_IN") (class "Default")
      (node (ref "IC6") (pin "22") (pinfunction "~OC0CRXD0PD2_22") (pintype "bidirectional"))
      (node (ref "IC8") (pin "1") (pinfunction "OE_1") (pintype "input"))
      (node (ref "R32") (pin "1") (pinfunction "1_1") (pintype "passive"))
    )
    (net (code "11") (name "/EN_CLOCK_OUT") (class "Default")
      (node (ref "IC6") (pin "6") (pinfunction "PB2/ADC10/DAC0_6") (pintype "bidirectional"))
      (node (ref "IC7") (pin "1") (pinfunction "OE_1") (pintype "input"))
      (node (ref "R33") (pin "1") (pinfunction "1_1") (pintype "passive"))
    )
    (net (code "12") (name "/FTDI_CTS") (class "Default")
      (node (ref "IC4") (pin "11") (pinfunction "~{CTS}_11") (pintype "input"))
      (node (ref "IC6") (pin "29") (pinfunction "~XCK0OC0BSCLPE1_29") (pintype "bidirectional"))
    )
    (net (code "13") (name "/FTDI_RTS") (class "Default")
      (node (ref "IC4") (pin "3") (pinfunction "~{RTS}_3") (pintype "output"))
      (node (ref "IC6") (pin "28") (pinfunction "~{OC0ASDAPE0}_28") (pintype "bidirectional"))
    )
    (net (code "14") (name "/FTDI_RXD") (class "Default")
      (node (ref "IC4") (pin "5") (pinfunction "RXD_5") (pintype "input"))
      (node (ref "IC6") (pin "33") (pinfunction "~TXD0OC0DPE3_33") (pintype "bidirectional"))
    )
    (net (code "15") (name "/FTDI_TXD") (class "Default")
      (node (ref "IC4") (pin "1") (pinfunction "TXD_1") (pintype "output"))
      (node (ref "IC6") (pin "32") (pinfunction "~RXD0OC0CPE2_32") (pintype "bidirectional"))
    )
    (net (code "16") (name "/IN_0_BNC") (class "Default")
      (node (ref "R20") (pin "1") (pinfunction "1_1") (pintype "passive"))
      (node (ref "R21") (pin "2") (pinfunction "2_2") (pintype "passive"))
      (node (ref "X5") (pin "1") (pinfunction "1_1") (pintype "passive"))
    )
    (net (code "17") (name "/IN_0_BNC_5V") (class "Default")
      (node (ref "C22") (pin "1") (pinfunction "1_1") (pintype "passive"))
      (node (ref "R20") (pin "2") (pinfunction "2_2") (pintype "passive"))
      (node (ref "U2") (pin "12") (pinfunction "4A_12") (pintype "bidirectional"))
      (node (ref "U4") (pin "2") (pinfunction "1A_2") (pintype "bidirectional"))
      (node (ref "U4") (pin "5") (pinfunction "2A_5") (pintype "bidirectional"))
    )
    (net (code "18") (name "/IN_CAM1_5V_TOL") (class "Default")
      (node (ref "R15") (pin "2") (pinfunction "2_2") (pintype "passive"))
      (node (ref "U3") (pin "2") (pinfunction "1A_2") (pintype "bidirectional"))
      (node (ref "X1") (pin "5") (pinfunction "5_5") (pintype "passive"))
    )
    (net (code "19") (name "/IN_CAM1_5V_TOL_PULLUP") (class "Default")
      (node (ref "R16") (pin "2") (pinfunction "2_2") (pintype "passive"))
      (node (ref "U3") (pin "5") (pinfunction "2A_5") (pintype "bidirectional"))
      (node (ref "X1") (pin "6") (pinfunction "6_6") (pintype "passive"))
    )
    (net (code "20") (name "/IN_CAM2_5V_TOL") (class "Default")
      (node (ref "R17") (pin "2") (pinfunction "2_2") (pintype "passive"))
      (node (ref "U3") (pin "9") (pinfunction "3A_9") (pintype "bidirectional"))
      (node (ref "X2") (pin "5") (pinfunction "5_5") (pintype "passive"))
    )
    (net (code "21") (name "/IN_CAM2_5V_TOL_PULLUP") (class "Default")
      (node (ref "R14") (pin "2") (pinfunction "2_2") (pintype "passive"))
      (node (ref "U3") (pin "12") (pinfunction "4A_12") (pintype "bidirectional"))
      (node (ref "X2") (pin "6") (pinfunction "6_6") (pintype "passive"))
    )
    (net (code "22") (name "/LED_CAM1") (class "Default")
      (node (ref "IC6") (pin "3") (pinfunction "PA7/ADC7/AC0-OUT_3") (pintype "bidirectional"))
      (node (ref "R24") (pin "1") (pinfunction "1_1") (pintype "passive"))
    )
    (net (code "23") (name "/LED_CAM2") (class "Default")
      (node (ref "IC6") (pin "17") (pinfunction "PC7/SCK/TXD1/CLKO/EVO_17") (pintype "bidirectional"))
      (node (ref "R25") (pin "1") (pinfunction "1_1") (pintype "passive"))
    )
    (net (code "24") (name "/LED_PWR") (class "Default")
      (node (ref "IC6") (pin "25") (pinfunction "~XCK1MOSIPD5_25") (pintype "bidirectional"))
      (node (ref "R28") (pin "1") (pinfunction "1_1") (pintype "passive"))
    )
    (net (code "25") (name "/LED_STATE") (class "Default")
      (node (ref "IC6") (pin "36") (pinfunction "PR0/XTAL2_36") (pintype "bidirectional"))
      (node (ref "R29") (pin "1") (pinfunction "1_1") (pintype "passive"))
    )
    (net (code "26") (name "/OUT0_BNC_5V") (class "Default")
      (node (ref "R18") (pin "2") (pinfunction "2_2") (pintype "passive"))
      (node (ref "U5") (pin "8") (pinfunction "3Y_8") (pintype "bidirectional"))
    )
    (net (code "27") (name "/OUT1_BNC_5V") (class "Default")
      (node (ref "R19") (pin "2") (pinfunction "2_2") (pintype "passive"))
      (node (ref "U5") (pin "11") (pinfunction "4Y_11") (pintype "bidirectional"))
    )
    (net (code "28") (name "/OUT_0_BNC") (class "Default")
      (node (ref "R18") (pin "1") (pinfunction "1_1") (pintype "passive"))
      (node (ref "X3") (pin "1") (pinfunction "1_1") (pintype "passive"))
    )
    (net (code "29") (name "/OUT_1_BNC") (class "Default")
      (node (ref "R19") (pin "1") (pinfunction "1_1") (pintype "passive"))
      (node (ref "X4") (pin "1") (pinfunction "1_1") (pintype "passive"))
    )
    (net (code "30") (name "/OUT_CAM0_TRIGGER_3V3") (class "Default")
      (node (ref "IC2") (pin "4") (pinfunction "O_4") (pintype "tri_state"))
      (node (ref "U2") (pin "3") (pinfunction "1Y_3") (pintype "bidirectional"))
      (node (ref "U5") (pin "2") (pinfunction "1A_2") (pintype "bidirectional"))
      (node (ref "X1") (pin "4") (pinfunction "4_4") (pintype "passive"))
    )
    (net (code "31") (name "/OUT_CAM0_TRIGGER_5V") (class "Default")
      (node (ref "U5") (pin "3") (pinfunction "1Y_3") (pintype "bidirectional"))
      (node (ref "X1") (pin "3") (pinfunction "3_3") (pintype "passive"))
    )
    (net (code "32") (name "/OUT_CAM1_TRIGGER_3V3") (class "Default")
      (node (ref "IC3") (pin "4") (pinfunction "O_4") (pintype "tri_state"))
      (node (ref "U2") (pin "6") (pinfunction "2Y_6") (pintype "bidirectional"))
      (node (ref "U5") (pin "5") (pinfunction "2A_5") (pintype "bidirectional"))
      (node (ref "X2") (pin "4") (pinfunction "4_4") (pintype "passive"))
    )
    (net (code "33") (name "/OUT_CAM1_TRIGGER_5V") (class "Default")
      (node (ref "U5") (pin "6") (pinfunction "2Y_6") (pintype "bidirectional"))
      (node (ref "X2") (pin "3") (pinfunction "3_3") (pintype "passive"))
    )
    (net (code "34") (name "/PDI_CLK") (class "Default")
      (node (ref "C37") (pin "1") (pinfunction "1_1") (pintype "passive"))
      (node (ref "IC6") (pin "35") (pinfunction "RESET/PDI-CLK_35") (pintype "input"))
      (node (ref "R34") (pin "1") (pinfunction "1_1") (pintype "passive"))
      (node (ref "SV1") (pin "5") (pinfunction "5_5") (pintype "passive"))
    )
    (net (code "35") (name "/PDI_DATA") (class "Default")
      (node (ref "IC6") (pin "34") (pinfunction "PDI-DATA_34") (pintype "bidirectional"))
      (node (ref "SV1") (pin "1") (pinfunction "1_1") (pintype "passive"))
    )
    (net (code "36") (name "/U_CAM0_TRIGGER_INV_ENBL") (class "Default")
      (node (ref "IC2") (pin "1") (pinfunction "OE_1") (pintype "input"))
      (node (ref "IC6") (pin "43") (pinfunction "PA3/ADC3_43") (pintype "bidirectional"))
      (node (ref "R6") (pin "2") (pinfunction "2_2") (pintype "passive"))
    )
    (net (code "37") (name "/U_CAM0_TRIGGER_N-INV-ENBL") (class "Default")
      (node (ref "IC6") (pin "44") (pinfunction "PA4/ADC4_44") (pintype "bidirectional"))
      (node (ref "R4") (pin "2") (pinfunction "2_2") (pintype "passive"))
      (node (ref "U2") (pin "1") (pinfunction "~{1OE}_1") (pintype "bidirectional"))
    )
    (net (code "38") (name "/U_CAM0_TRIGGER_TO_OUT0_BNC_ENBL") (class "Default")
      (node (ref "IC6") (pin "4") (pinfunction "PB0/ADC8/AREF_4") (pintype "bidirectional"))
      (node (ref "U4") (pin "10") (pinfunction "~{3OE}_10") (pintype "bidirectional"))
    )
    (net (code "39") (name "/U_CAM1_TRIGGER_INV_ENBL") (class "Default")
      (node (ref "IC3") (pin "1") (pinfunction "OE_1") (pintype "input"))
      (node (ref "IC6") (pin "14") (pinfunction "PC4/OC1A/#SS_14") (pintype "bidirectional"))
      (node (ref "R7") (pin "2") (pinfunction "2_2") (pintype "passive"))
    )
    (net (code "40") (name "/U_CAM1_TRIGGER_N-INV_ENBL") (class "Default")
      (node (ref "IC6") (pin "15") (pinfunction "PC5/OC1B/MOSI/XCK1_15") (pintype "bidirectional"))
      (node (ref "R2") (pin "2") (pinfunction "2_2") (pintype "passive"))
      (node (ref "U2") (pin "4") (pinfunction "~{2OE}_4") (pintype "bidirectional"))
    )
    (net (code "41") (name "/U_CAM1_TRIGGER_TO_OUT1_BNC_ENBL") (class "Default")
      (node (ref "IC6") (pin "5") (pinfunction "PB1/ADC9_5") (pintype "bidirectional"))
      (node (ref "U4") (pin "13") (pinfunction "~{4OE}_13") (pintype "bidirectional"))
    )
    (net (code "42") (name "/U_IN0_BNC_5V") (class "Default")
      (node (ref "IC6") (pin "7") (pinfunction "PB3/ADC11/DAC1_7") (pintype "bidirectional"))
      (node (ref "U2") (pin "11") (pinfunction "4Y_11") (pintype "bidirectional"))
    )
    (net (code "43") (name "/U_IN0_TO_CAM0_TRIGGER_ENBL") (class "Default")
      (node (ref "IC6") (pin "1") (pinfunction "PA5/ADC5_1") (pintype "bidirectional"))
      (node (ref "U4") (pin "1") (pinfunction "~{1OE}_1") (pintype "bidirectional"))
    )
    (net (code "44") (name "/U_IN0_TO_CAM1_TRIGGER_ENBL") (class "Default")
      (node (ref "IC6") (pin "2") (pinfunction "PA6/ADC6_2") (pintype "bidirectional"))
      (node (ref "U4") (pin "4") (pinfunction "~{2OE}_4") (pintype "bidirectional"))
    )
    (net (code "45") (name "/U_IN_CAM1_STROBE_5V") (class "Default")
      (node (ref "IC6") (pin "40") (pinfunction "PA0/ADC0/AREF_40") (pintype "bidirectional"))
      (node (ref "U3") (pin "3") (pinfunction "1Y_3") (pintype "bidirectional"))
    )
    (net (code "46") (name "/U_IN_CAM1_STROBE_PULLUP_5V") (class "Default")
      (node (ref "IC6") (pin "41") (pinfunction "PA1/ADC1_41") (pintype "bidirectional"))
      (node (ref "U3") (pin "6") (pinfunction "2Y_6") (pintype "bidirectional"))
    )
    (net (code "47") (name "/U_IN_CAM2_STROBE_5V") (class "Default")
      (node (ref "IC6") (pin "13") (pinfunction "PC3/OC0D/TXD0_13") (pintype "bidirectional"))
      (node (ref "U3") (pin "8") (pinfunction "3Y_8") (pintype "bidirectional"))
    )
    (net (code "48") (name "/U_IN_CAM2_STROBE_PULLUP_5V") (class "Default")
      (node (ref "IC6") (pin "12") (pinfunction "PC2/OC0C/RXD0_12") (pintype "bidirectional"))
      (node (ref "U3") (pin "11") (pinfunction "4Y_11") (pintype "bidirectional"))
    )
    (net (code "49") (name "/U_IO_CAM0_TRIGGER") (class "Default")
      (node (ref "IC2") (pin "2") (pinfunction "I_2") (pintype "input"))
      (node (ref "IC6") (pin "20") (pinfunction "~{OC0APD0}_20") (pintype "bidirectional"))
      (node (ref "R3") (pin "2") (pinfunction "2_2") (pintype "passive"))
      (node (ref "U2") (pin "2") (pinfunction "1A_2") (pintype "bidirectional"))
      (node (ref "U4") (pin "3") (pinfunction "1Y_3") (pintype "bidirectional"))
      (node (ref "U4") (pin "9") (pinfunction "3A_9") (pintype "bidirectional"))
    )
    (net (code "50") (name "/U_IO_CAM1_TRIGGER") (class "Default")
      (node (ref "IC3") (pin "2") (pinfunction "I_2") (pintype "input"))
      (node (ref "IC6") (pin "10") (pinfunction "PC0/OC0A/SDA_10") (pintype "bidirectional"))
      (node (ref "R5") (pin "2") (pinfunction "2_2") (pintype "passive"))
      (node (ref "U2") (pin "5") (pinfunction "2A_5") (pintype "bidirectional"))
      (node (ref "U4") (pin "12") (pinfunction "4A_12") (pintype "bidirectional"))
      (node (ref "U4") (pin "6") (pinfunction "2Y_6") (pintype "bidirectional"))
    )
    (net (code "51") (name "/U_OUT0_BNC_5V") (class "Default")
      (node (ref "IC6") (pin "21") (pinfunction "~OC0BXCK0PD1_21") (pintype "bidirectional"))
      (node (ref "R10") (pin "1") (pinfunction "1_1") (pintype "passive"))
      (node (ref "U4") (pin "8") (pinfunction "3Y_8") (pintype "bidirectional"))
      (node (ref "U5") (pin "9") (pinfunction "3A_9") (pintype "bidirectional"))
    )
    (net (code "52") (name "/U_OUT1_BNC_5V") (class "Default")
      (node (ref "IC6") (pin "11") (pinfunction "PC1/OC0B/XCK0/SCL_11") (pintype "bidirectional"))
      (node (ref "R11") (pin "1") (pinfunction "1_1") (pintype "passive"))
      (node (ref "U4") (pin "11") (pinfunction "4Y_11") (pintype "bidirectional"))
      (node (ref "U5") (pin "12") (pinfunction "4A_12") (pintype "bidirectional"))
    )
    (net (code "53") (name "/VREF") (class "Default")
      (node (ref "R12") (pin "1") (pinfunction "1_1") (pintype "passive"))
      (node (ref "R13") (pin "2") (pinfunction "2_2") (pintype "passive"))
      (node (ref "U1") (pin "12") (pinfunction "FB_12") (pintype "bidirectional"))
    )
    (net (code "54") (name "GND") (class "Default")
      (node (ref "C1") (pin "2") (pinfunction "2_2") (pintype "passive"))
      (node (ref "C10") (pin "2") (pinfunction "2_2") (pintype "passive"))
      (node (ref "C12") (pin "2") (pinfunction "2_2") (pintype "passive"))
      (node (ref "C13") (pin "2") (pinfunction "2_2") (pintype "passive"))
      (node (ref "C14") (pin "2") (pinfunction "2_2") (pintype "passive"))
      (node (ref "C15") (pin "2") (pinfunction "2_2") (pintype "passive"))
      (node (ref "C16") (pin "2") (pinfunction "2_2") (pintype "passive"))
      (node (ref "C17") (pin "-") (pinfunction "-_-") (pintype "passive"))
      (node (ref "C18") (pin "2") (pinfunction "2_2") (pintype "passive"))
      (node (ref "C19") (pin "2") (pinfunction "2_2") (pintype "passive"))
      (node (ref "C2") (pin "2") (pinfunction "2_2") (pintype "passive"))
      (node (ref "C20") (pin "2") (pinfunction "2_2") (pintype "passive"))
      (node (ref "C21") (pin "2") (pinfunction "2_2") (pintype "passive"))
      (node (ref "C22") (pin "2") (pinfunction "2_2") (pintype "passive"))
      (node (ref "C23") (pin "2") (pinfunction "2_2") (pintype "passive"))
      (node (ref "C24") (pin "2") (pinfunction "2_2") (pintype "passive"))
      (node (ref "C25") (pin "2") (pinfunction "2_2") (pintype "passive"))
      (node (ref "C26") (pin "2") (pinfunction "2_2") (pintype "passive"))
      (node (ref "C27") (pin "2") (pinfunction "2_2") (pintype "passive"))
      (node (ref "C28") (pin "2") (pinfunction "2_2") (pintype "passive"))
      (node (ref "C29") (pin "2") (pinfunction "2_2") (pintype "passive"))
      (node (ref "C3") (pin "2") (pinfunction "2_2") (pintype "passive"))
      (node (ref "C30") (pin "2") (pinfunction "2_2") (pintype "passive"))
      (node (ref "C31") (pin "2") (pinfunction "2_2") (pintype "passive"))
      (node (ref "C32") (pin "2") (pinfunction "2_2") (pintype "passive"))
      (node (ref "C33") (pin "2") (pinfunction "2_2") (pintype "passive"))
      (node (ref "C34") (pin "2") (pinfunction "2_2") (pintype "passive"))
      (node (ref "C35") (pin "2") (pinfunction "2_2") (pintype "passive"))
      (node (ref "C36") (pin "2") (pinfunction "2_2") (pintype "passive"))
      (node (ref "C37") (pin "2") (pinfunction "2_2") (pintype "passive"))
      (node (ref "C4") (pin "2") (pinfunction "2_2") (pintype "passive"))
      (node (ref "C5") (pin "2") (pinfunction "2_2") (pintype "passive"))
      (node (ref "C6") (pin "2") (pinfunction "2_2") (pintype "passive"))
      (node (ref "C7") (pin "-") (pinfunction "-_-") (pintype "passive"))
      (node (ref "C8") (pin "2") (pinfunction "2_2") (pintype "passive"))
      (node (ref "C9") (pin "2") (pinfunction "2_2") (pintype "passive"))
      (node (ref "CLOCK_IN") (pin "5") (pinfunction "5_5") (pintype "passive"))
      (node (ref "D1") (pin "A") (pinfunction "A_A") (pintype "passive"))
      (node (ref "GND1_TP") (pin "TP") (pinfunction "TP_TP") (pintype "input"))
      (node (ref "GND2_TP") (pin "TP") (pinfunction "TP_TP") (pintype "input"))
      (node (ref "IC1") (pin "P$2") (pinfunction "GND_P$2") (pintype "bidirectional"))
      (node (ref "IC10") (pin "4") (pinfunction "AGND_4") (pintype "bidirectional"))
      (node (ref "IC2") (pin "3") (pinfunction "GND_3") (pintype "power_in"))
      (node (ref "IC3") (pin "3") (pinfunction "GND_3") (pintype "power_in"))
      (node (ref "IC4") (pin "18") (pinfunction "GND_18") (pintype "power_in"))
      (node (ref "IC4") (pin "21") (pinfunction "GND_21") (pintype "power_in"))
      (node (ref "IC4") (pin "25") (pinfunction "GND_25") (pintype "power_in"))
      (node (ref "IC4") (pin "26") (pinfunction "TEST_26") (pintype "input"))
      (node (ref "IC4") (pin "7") (pinfunction "GND_7") (pintype "power_in"))
      (node (ref "IC5") (pin "2") (pinfunction "GND_2") (pintype "bidirectional"))
      (node (ref "IC6") (pin "18") (pinfunction "GND_18") (pintype "power_in"))
      (node (ref "IC6") (pin "30") (pinfunction "GND_30") (pintype "power_in"))
      (node (ref "IC6") (pin "38") (pinfunction "GND_38") (pintype "power_in"))
      (node (ref "IC6") (pin "8") (pinfunction "GND_8") (pintype "power_in"))
      (node (ref "IC7") (pin "3") (pinfunction "GND_3") (pintype "power_in"))
      (node (ref "IC8") (pin "3") (pinfunction "GND_3") (pintype "power_in"))
      (node (ref "IC9") (pin "2") (pinfunction "GND_2") (pintype "bidirectional"))
      (node (ref "OSC1") (pin "P$2") (pinfunction "GND_P$2") (pintype "passive"))
      (node (ref "PWR1") (pin "P2") (pinfunction "2_P2") (pintype "passive"))
      (node (ref "PWR1") (pin "P3") (pinfunction "3_P3") (pintype "passive"))
      (node (ref "R1") (pin "2") (pinfunction "2_2") (pintype "passive"))
      (node (ref "R10") (pin "2") (pinfunction "2_2") (pintype "passive"))
      (node (ref "R11") (pin "2") (pinfunction "2_2") (pintype "passive"))
      (node (ref "R13") (pin "1") (pinfunction "1_1") (pintype "passive"))
      (node (ref "R15") (pin "1") (pinfunction "1_1") (pintype "passive"))
      (node (ref "R17") (pin "1") (pinfunction "1_1") (pintype "passive"))
      (node (ref "R2") (pin "1") (pinfunction "1_1") (pintype "passive"))
      (node (ref "R21") (pin "1") (pinfunction "1_1") (pintype "passive"))
      (node (ref "R22") (pin "2") (pinfunction "2_2") (pintype "passive"))
      (node (ref "R23") (pin "2") (pinfunction "2_2") (pintype "passive"))
      (node (ref "R3") (pin "1") (pinfunction "1_1") (pintype "passive"))
      (node (ref "R32") (pin "2") (pinfunction "2_2") (pintype "passive"))
      (node (ref "R4") (pin "1") (pinfunction "1_1") (pintype "passive"))
      (node (ref "R5") (pin "1") (pinfunction "1_1") (pintype "passive"))
      (node (ref "SV1") (pin "6") (pinfunction "6_6") (pintype "passive"))
      (node (ref "T1") (pin "2") (pinfunction "E_2") (pintype "passive"))
      (node (ref "T2") (pin "2") (pinfunction "E_2") (pintype "passive"))
      (node (ref "T3") (pin "2") (pinfunction "E_2") (pintype "passive"))
      (node (ref "T4") (pin "2") (pinfunction "E_2") (pintype "passive"))
      (node (ref "U1") (pin "1") (pinfunction "GND_1") (pintype "bidirectional"))
      (node (ref "U1") (pin "14") (pinfunction "SYNC_14") (pintype "bidirectional"))
      (node (ref "U1") (pin "16") (pinfunction "GND_16") (pintype "bidirectional"))
      (node (ref "U1") (pin "17") (pinfunction "GND_17") (pintype "bidirectional"))
      (node (ref "U1") (pin "8") (pinfunction "GND_8") (pintype "bidirectional"))
      (node (ref "U1") (pin "9") (pinfunction "GND_9") (pintype "bidirectional"))
      (node (ref "U2") (pin "13") (pinfunction "~{4OE}_13") (pintype "bidirectional"))
      (node (ref "U2") (pin "7") (pinfunction "GND_7") (pintype "bidirectional"))
      (node (ref "U3") (pin "1") (pinfunction "~{1OE}_1") (pintype "bidirectional"))
      (node (ref "U3") (pin "10") (pinfunction "~{3OE}_10") (pintype "bidirectional"))
      (node (ref "U3") (pin "13") (pinfunction "~{4OE}_13") (pintype "bidirectional"))
      (node (ref "U3") (pin "4") (pinfunction "~{2OE}_4") (pintype "bidirectional"))
      (node (ref "U3") (pin "7") (pinfunction "GND_7") (pintype "bidirectional"))
      (node (ref "U4") (pin "7") (pinfunction "GND_7") (pintype "bidirectional"))
      (node (ref "U5") (pin "1") (pinfunction "~{1OE}_1") (pintype "bidirectional"))
      (node (ref "U5") (pin "10") (pinfunction "~{3OE}_10") (pintype "bidirectional"))
      (node (ref "U5") (pin "13") (pinfunction "~{4OE}_13") (pintype "bidirectional"))
      (node (ref "U5") (pin "4") (pinfunction "~{2OE}_4") (pintype "bidirectional"))
      (node (ref "U5") (pin "7") (pinfunction "GND_7") (pintype "bidirectional"))
      (node (ref "USB1") (pin "P$5") (pinfunction "5_P$5") (pintype "bidirectional"))
      (node (ref "X1") (pin "2") (pinfunction "2_2") (pintype "passive"))
      (node (ref "X1") (pin "7") (pinfunction "7_7") (pintype "passive"))
      (node (ref "X2") (pin "2") (pinfunction "2_2") (pintype "passive"))
      (node (ref "X2") (pin "7") (pinfunction "7_7") (pintype "passive"))
      (node (ref "X3") (pin "2") (pinfunction "2_2") (pintype "passive"))
      (node (ref "X3") (pin "3") (pinfunction "2_3") (pintype "passive"))
      (node (ref "X4") (pin "2") (pinfunction "2_2") (pintype "passive"))
      (node (ref "X4") (pin "3") (pinfunction "2_3") (pintype "passive"))
      (node (ref "X5") (pin "2") (pinfunction "2_2") (pintype "passive"))
      (node (ref "X5") (pin "3") (pinfunction "2_3") (pintype "passive"))
    )
    (net (code "55") (name "Net-(C11-Pad2)") (class "Default")
      (node (ref "C11") (pin "2") (pinfunction "2_2") (pintype "passive"))
      (node (ref "D1") (pin "C") (pinfunction "C_C") (pintype "passive"))
      (node (ref "L1") (pin "2") (pinfunction "2_2") (pintype "passive"))
      (node (ref "U1") (pin "5") (pinfunction "SW_5") (pintype "bidirectional"))
      (node (ref "U1") (pin "6") (pinfunction "SW_6") (pintype "bidirectional"))
    )
    (net (code "56") (name "Net-(CLOCK_IN-Pad1)") (class "Default")
      (node (ref "CLOCK_IN") (pin "1") (pinfunction "1_1") (pintype "passive"))
      (node (ref "R35") (pin "2") (pinfunction "2_2") (pintype "passive"))
      (node (ref "R36") (pin "1") (pinfunction "1_1") (pintype "passive"))
    )
    (net (code "57") (name "Net-(IC4-3V3OUT)") (class "Default")
      (node (ref "C14") (pin "1") (pinfunction "1_1") (pintype "passive"))
      (node (ref "IC4") (pin "17") (pinfunction "3V3OUT_17") (pintype "output"))
    )
    (net (code "58") (name "Net-(IC4-USBDM)") (class "Default")
      (node (ref "C13") (pin "1") (pinfunction "1_1") (pintype "passive"))
      (node (ref "IC1") (pin "P$6") (pinfunction "IO1_P$6") (pintype "bidirectional"))
      (node (ref "IC4") (pin "16") (pinfunction "USBDM_16") (pintype "bidirectional"))
    )
    (net (code "59") (name "Net-(IC4-USBDP)") (class "Default")
      (node (ref "C10") (pin "1") (pinfunction "1_1") (pintype "passive"))
      (node (ref "IC1") (pin "P$4") (pinfunction "IO2_P$4") (pintype "bidirectional"))
      (node (ref "IC4") (pin "15") (pinfunction "USBDP_15") (pintype "bidirectional"))
    )
    (net (code "60") (name "Net-(IC6-PR1{slash}XTAL1)") (class "Default")
      (node (ref "IC6") (pin "37") (pinfunction "PR1/XTAL1_37") (pintype "bidirectional"))
      (node (ref "OSC1") (pin "P$3") (pinfunction "OUTPUT_P$3") (pintype "passive"))
    )
    (net (code "61") (name "Net-(IC9-OUT)") (class "Default")
      (node (ref "C35") (pin "1") (pinfunction "1_1") (pintype "passive"))
      (node (ref "C36") (pin "1") (pinfunction "1_1") (pintype "passive"))
      (node (ref "IC9") (pin "5") (pinfunction "OUT_5") (pintype "bidirectional"))
      (node (ref "R35") (pin "1") (pinfunction "1_1") (pintype "passive"))
    )
    (net (code "62") (name "Net-(IC10-A1)") (class "Default")
      (node (ref "IC10") (pin "2") (pinfunction "A1_2") (pintype "bidirectional"))
      (node (ref "IC7") (pin "4") (pinfunction "O_4") (pintype "tri_state"))
      (node (ref "IC8") (pin "4") (pinfunction "O_4") (pintype "tri_state"))
    )
    (net (code "63") (name "Net-(IC10-B1)") (class "Default")
      (node (ref "CLOCK_OUT") (pin "4") (pinfunction "4_4") (pintype "passive"))
      (node (ref "IC10") (pin "6") (pinfunction "B1_6") (pintype "bidirectional"))
    )
    (net (code "64") (name "Net-(IC10-BGND)") (class "Default")
      (node (ref "C38") (pin "2") (pinfunction "2_2") (pintype "passive"))
      (node (ref "CLOCK_OUT") (pin "5") (pinfunction "5_5") (pintype "passive"))
      (node (ref "IC10") (pin "5") (pinfunction "BGND_5") (pintype "bidirectional"))
    )
    (net (code "65") (name "Net-(IC10-BVDD)") (class "Default")
      (node (ref "C38") (pin "1") (pinfunction "1_1") (pintype "passive"))
      (node (ref "CLOCK_OUT") (pin "1") (pinfunction "1_1") (pintype "passive"))
      (node (ref "IC10") (pin "8") (pinfunction "BVDD_8") (pintype "bidirectional"))
    )
    (net (code "66") (name "Net-(LED1A-C)") (class "Default")
      (node (ref "LED1") (pin "C1") (pinfunction "C_C1") (pintype "passive"))
      (node (ref "R27") (pin "1") (pinfunction "1_1") (pintype "passive"))
    )
    (net (code "67") (name "Net-(LED1B-C)") (class "Default")
      (node (ref "LED1") (pin "C2") (pinfunction "C_C2") (pintype "passive"))
      (node (ref "R26") (pin "1") (pinfunction "1_1") (pintype "passive"))
    )
    (net (code "68") (name "Net-(LED2A-C)") (class "Default")
      (node (ref "LED2") (pin "C1") (pinfunction "C_C1") (pintype "passive"))
      (node (ref "R31") (pin "1") (pinfunction "1_1") (pintype "passive"))
    )
    (net (code "69") (name "Net-(LED2B-C)") (class "Default")
      (node (ref "LED2") (pin "C2") (pinfunction "C_C2") (pintype "passive"))
      (node (ref "R30") (pin "1") (pinfunction "1_1") (pintype "passive"))
    )
    (net (code "70") (name "Net-(T1-B)") (class "Default")
      (node (ref "R24") (pin "2") (pinfunction "2_2") (pintype "passive"))
      (node (ref "T1") (pin "1") (pinfunction "B_1") (pintype "passive"))
    )
    (net (code "71") (name "Net-(T1-C)") (class "Default")
      (node (ref "R26") (pin "2") (pinfunction "2_2") (pintype "passive"))
      (node (ref "T1") (pin "3") (pinfunction "C_3") (pintype "passive"))
    )
    (net (code "72") (name "Net-(T2-B)") (class "Default")
      (node (ref "R25") (pin "2") (pinfunction "2_2") (pintype "passive"))
      (node (ref "T2") (pin "1") (pinfunction "B_1") (pintype "passive"))
    )
    (net (code "73") (name "Net-(T2-C)") (class "Default")
      (node (ref "R27") (pin "2") (pinfunction "2_2") (pintype "passive"))
      (node (ref "T2") (pin "3") (pinfunction "C_3") (pintype "passive"))
    )
    (net (code "74") (name "Net-(T3-B)") (class "Default")
      (node (ref "R28") (pin "2") (pinfunction "2_2") (pintype "passive"))
      (node (ref "T3") (pin "1") (pinfunction "B_1") (pintype "passive"))
    )
    (net (code "75") (name "Net-(T3-C)") (class "Default")
      (node (ref "R30") (pin "2") (pinfunction "2_2") (pintype "passive"))
      (node (ref "T3") (pin "3") (pinfunction "C_3") (pintype "passive"))
    )
    (net (code "76") (name "Net-(T4-B)") (class "Default")
      (node (ref "R29") (pin "2") (pinfunction "2_2") (pintype "passive"))
      (node (ref "T4") (pin "1") (pinfunction "B_1") (pintype "passive"))
    )
    (net (code "77") (name "Net-(T4-C)") (class "Default")
      (node (ref "R31") (pin "2") (pinfunction "2_2") (pintype "passive"))
      (node (ref "T4") (pin "3") (pinfunction "C_3") (pintype "passive"))
    )
    (net (code "78") (name "Net-(U1-BOOST)") (class "Default")
      (node (ref "C11") (pin "1") (pinfunction "1_1") (pintype "passive"))
      (node (ref "D2") (pin "C") (pinfunction "C_C") (pintype "passive"))
      (node (ref "U1") (pin "2") (pinfunction "BOOST_2") (pintype "bidirectional"))
    )
    (net (code "79") (name "Net-(U2-~{3OE})") (class "Default")
      (node (ref "R8") (pin "2") (pinfunction "2_2") (pintype "passive"))
      (node (ref "U2") (pin "10") (pinfunction "~{3OE}_10") (pintype "bidirectional"))
    )
    (net (code "80") (name "Net-(USB1-2)") (class "Default")
      (node (ref "IC1") (pin "P$1") (pinfunction "IO1_P$1") (pintype "bidirectional"))
      (node (ref "USB1") (pin "P$2") (pinfunction "2_P$2") (pintype "bidirectional"))
    )
    (net (code "81") (name "Net-(USB1-3)") (class "Default")
      (node (ref "IC1") (pin "P$3") (pinfunction "IO2_P$3") (pintype "bidirectional"))
      (node (ref "USB1") (pin "P$3") (pinfunction "3_P$3") (pintype "bidirectional"))
    )
    (net (code "82") (name "Net-(USB1-P$1)") (class "Default")
      (node (ref "R1") (pin "1") (pinfunction "1_1") (pintype "passive"))
      (node (ref "USB1") (pin "SHIELD_1") (pinfunction "P$1_SHIELD_1") (pintype "bidirectional"))
    )
    (net (code "83") (name "Net-(USB1-P$4)") (class "Default")
      (node (ref "C1") (pin "1") (pinfunction "1_1") (pintype "passive"))
      (node (ref "USB1") (pin "SHIELD_4") (pinfunction "P$4_SHIELD_4") (pintype "bidirectional"))
    )
    (net (code "84") (name "V+") (class "Default")
      (node (ref "C17") (pin "+") (pinfunction "+_+") (pintype "passive"))
      (node (ref "C18") (pin "1") (pinfunction "1_1") (pintype "passive"))
      (node (ref "D2") (pin "A") (pinfunction "A_A") (pintype "passive"))
      (node (ref "L1") (pin "1") (pinfunction "1_1") (pintype "passive"))
      (node (ref "R12") (pin "2") (pinfunction "2_2") (pintype "passive"))
      (node (ref "X1") (pin "8") (pinfunction "8_8") (pintype "passive"))
      (node (ref "X2") (pin "8") (pinfunction "8_8") (pintype "passive"))
    )
    (net (code "85") (name "unconnected-(IC4-CBUS0-Pad23)") (class "Default")
      (node (ref "IC4") (pin "23") (pinfunction "CBUS0_23") (pintype "passive"))
    )
    (net (code "86") (name "unconnected-(IC4-CBUS1-Pad22)") (class "Default")
      (node (ref "IC4") (pin "22") (pinfunction "CBUS1_22") (pintype "passive"))
    )
    (net (code "87") (name "unconnected-(IC4-CBUS2-Pad13)") (class "Default")
      (node (ref "IC4") (pin "13") (pinfunction "CBUS2_13") (pintype "passive"))
    )
    (net (code "88") (name "unconnected-(IC4-CBUS3-Pad14)") (class "Default")
      (node (ref "IC4") (pin "14") (pinfunction "CBUS3_14") (pintype "passive"))
    )
    (net (code "89") (name "unconnected-(IC4-CBUS4-Pad12)") (class "Default")
      (node (ref "IC4") (pin "12") (pinfunction "CBUS4_12") (pintype "passive"))
    )
    (net (code "90") (name "unconnected-(IC4-OSCI-Pad27)") (class "Default")
      (node (ref "IC4") (pin "27") (pinfunction "OSCI_27") (pintype "passive"))
    )
    (net (code "91") (name "unconnected-(IC4-OSCO-Pad28)") (class "Default")
      (node (ref "IC4") (pin "28") (pinfunction "OSCO_28") (pintype "output"))
    )
    (net (code "92") (name "unconnected-(IC4-~{DCD}-Pad10)") (class "Default")
      (node (ref "IC4") (pin "10") (pinfunction "~{DCD}_10") (pintype "passive"))
    )
    (net (code "93") (name "unconnected-(IC4-~{DSR}-Pad9)") (class "Default")
      (node (ref "IC4") (pin "9") (pinfunction "~{DSR}_9") (pintype "passive"))
    )
    (net (code "94") (name "unconnected-(IC4-~{DTR}-Pad2)") (class "Default")
      (node (ref "IC4") (pin "2") (pinfunction "~{DTR}_2") (pintype "passive"))
    )
    (net (code "95") (name "unconnected-(IC4-~{RESET}-Pad19)") (class "Default")
      (node (ref "IC4") (pin "19") (pinfunction "~{RESET}_19") (pintype "passive"))
    )
    (net (code "96") (name "unconnected-(IC4-~{RI}-Pad6)") (class "Default")
      (node (ref "IC4") (pin "6") (pinfunction "~{RI}_6") (pintype "passive"))
    )
    (net (code "97") (name "unconnected-(IC5-N{slash}C-Pad4)") (class "Default")
      (node (ref "IC5") (pin "4") (pinfunction "N/C_4") (pintype "bidirectional"))
    )
    (net (code "98") (name "unconnected-(IC6-PA2{slash}ADC2-Pad42)") (class "Default")
      (node (ref "IC6") (pin "42") (pinfunction "PA2/ADC2_42") (pintype "bidirectional"))
    )
    (net (code "99") (name "unconnected-(IC6-PC6{slash}MISO{slash}RXD1-Pad16)") (class "Default")
      (node (ref "IC6") (pin "16") (pinfunction "PC6/MISO/RXD1_16") (pintype "bidirectional"))
    )
    (net (code "100") (name "unconnected-(IC9-N{slash}C-Pad4)") (class "Default")
      (node (ref "IC9") (pin "4") (pinfunction "N/C_4") (pintype "bidirectional"))
    )
    (net (code "101") (name "unconnected-(IC10-AVDD{slash}NC-Pad3)") (class "Default")
      (node (ref "IC10") (pin "3") (pinfunction "AVDD/NC_3") (pintype "bidirectional"))
    )
    (net (code "102") (name "unconnected-(IC10-BGND{slash}NC-Pad7)") (class "Default")
      (node (ref "IC10") (pin "7") (pinfunction "BGND/NC_7") (pintype "bidirectional"))
    )
    (net (code "103") (name "unconnected-(OSC1-STANDBY#-PadP$1)") (class "Default")
      (node (ref "OSC1") (pin "P$1") (pinfunction "STANDBY#_P$1") (pintype "passive"))
    )
    (net (code "104") (name "unconnected-(SV1-Pad3)") (class "Default")
      (node (ref "SV1") (pin "3") (pinfunction "3_3") (pintype "passive"))
    )
    (net (code "105") (name "unconnected-(SV1-Pad4)") (class "Default")
      (node (ref "SV1") (pin "4") (pinfunction "4_4") (pintype "passive"))
    )
    (net (code "106") (name "unconnected-(U1-NC7-Pad7)") (class "Default")
      (node (ref "U1") (pin "7") (pinfunction "NC7_7") (pintype "bidirectional"))
    )
    (net (code "107") (name "unconnected-(U1-NC10-Pad10)") (class "Default")
      (node (ref "U1") (pin "10") (pinfunction "NC10_10") (pintype "bidirectional"))
    )
    (net (code "108") (name "unconnected-(U1-NC15-Pad15)") (class "Default")
      (node (ref "U1") (pin "15") (pinfunction "NC15_15") (pintype "bidirectional"))
    )
    (net (code "109") (name "unconnected-(U1-VC-Pad13)") (class "Default")
      (node (ref "U1") (pin "13") (pinfunction "VC_13") (pintype "bidirectional"))
    )
    (net (code "110") (name "unconnected-(U1-~{SHDN}-Pad11)") (class "Default")
      (node (ref "U1") (pin "11") (pinfunction "~{SHDN}_11") (pintype "bidirectional"))
    )
    (net (code "111") (name "unconnected-(U2-3A-Pad9)") (class "Default")
      (node (ref "U2") (pin "9") (pinfunction "3A_9") (pintype "bidirectional"))
    )
    (net (code "112") (name "unconnected-(U2-3Y-Pad8)") (class "Default")
      (node (ref "U2") (pin "8") (pinfunction "3Y_8") (pintype "bidirectional"))
    )
    (net (code "113") (name "unconnected-(USB1-4-PadP$4)") (class "Default")
      (node (ref "USB1") (pin "P$4") (pinfunction "4_P$4") (pintype "bidirectional"))
    )
    (net (code "114") (name "unconnected-(USB1-P$2-PadSHIELD_2)") (class "Default")
      (node (ref "USB1") (pin "SHIELD_2") (pinfunction "P$2_SHIELD_2") (pintype "bidirectional"))
    )
    (net (code "115") (name "unconnected-(USB1-P$3-PadSHIELD_3)") (class "Default")
      (node (ref "USB1") (pin "SHIELD_3") (pinfunction "P$3_SHIELD_3") (pintype "bidirectional"))
    )
  )
)
